# design.net
KiCad netlist of a schematic drawn in Altium Designer
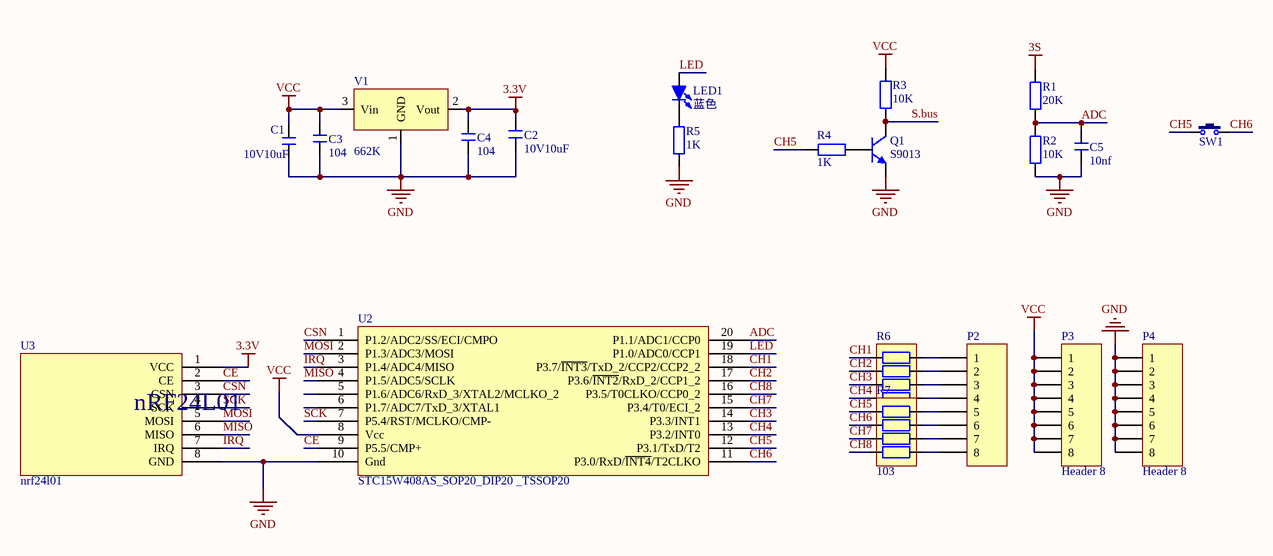
[diagram p0: 原理图.SchDoc]

(export (version "E")
  (design (tool "Eeschema 10.0.6"))
  (components
    (comp (ref "C1")
      (value "10V10uF")
      (footprint "C 0805_L")
      (description "无极性贴片电容")
      (fields (field (name "版权归属") "源创客"))
      (libsource (lib "3.1   - 电阻-电容-电感") (part "C"))
    )
    (comp (ref "C2")
      (value "10V10uF")
      (footprint "C 0805_L")
      (description "无极性贴片电容")
      (fields (field (name "版权归属") "源创客"))
      (libsource (lib "3.1   - 电阻-电容-电感") (part "C"))
    )
    (comp (ref "C3")
      (value "104")
      (footprint "C 0603_L")
      (description "无极性贴片电容")
      (fields (field (name "版权归属") "源创客"))
      (libsource (lib "3.1   - 电阻-电容-电感") (part "C"))
    )
    (comp (ref "C4")
      (value "104")
      (footprint "C 0603_L")
      (description "无极性贴片电容")
      (fields (field (name "版权归属") "源创客"))
      (libsource (lib "3.1   - 电阻-电容-电感") (part "C"))
    )
    (comp (ref "C5")
      (value "10nf")
      (footprint "C 0603_L")
      (description "无极性贴片电容")
      (fields (field (name "版权归属") "源创客"))
      (libsource (lib "3.1   - 电阻-电容-电感") (part "C"))
    )
    (comp (ref "LED1")
      (value "蓝色")
      (footprint "LED 0603B")
      (description "贴片LED")
      (fields (field (name "版权归属") "源创客"))
      (libsource (lib "9.1   - LED") (part "LED-SMD"))
    )
    (comp (ref "P2")
      (value "Header 8")
      (footprint "HDR2.54-LI-8P")
      (description "Header, 8-Pin")
      (fields (field (name "PUBLISHER") "Altium Limited"))
      (libsource (lib "Miscellaneous Connectors") (part "Header 8"))
    )
    (comp (ref "P3")
      (value "Header 8")
      (footprint "HDR2.54-LI-8P")
      (description "Header, 8-Pin")
      (fields (field (name "PUBLISHER") "Altium Limited"))
      (libsource (lib "Miscellaneous Connectors") (part "Header 8"))
    )
    (comp (ref "P4")
      (value "Header 8")
      (footprint "HDR2.54-LI-8P")
      (description "Header, 8-Pin")
      (fields (field (name "PUBLISHER") "Altium Limited"))
      (libsource (lib "Miscellaneous Connectors") (part "Header 8"))
    )
    (comp (ref "Q1")
      (value "S9013")
      (footprint "SOT23-3N")
      (description "低频放大-NPN型")
      (fields (field (name "版权归属") "源创客"))
      (libsource (lib "6.2   - 三极管") (part "9013-SMD"))
    )
    (comp (ref "R1")
      (value "20K")
      (footprint "R 0603_L")
      (description "贴片电阻")
      (fields (field (name "版权归属") "源创客"))
      (libsource (lib "3.1   - 电阻-电容-电感") (part "R"))
    )
    (comp (ref "R2")
      (value "10K")
      (footprint "R 0603_L")
      (description "贴片电阻")
      (fields (field (name "版权归属") "源创客"))
      (libsource (lib "3.1   - 电阻-电容-电感") (part "R"))
    )
    (comp (ref "R3")
      (value "10K")
      (footprint "R 0603_L")
      (description "贴片电阻")
      (fields (field (name "版权归属") "源创客"))
      (libsource (lib "3.1   - 电阻-电容-电感") (part "R"))
    )
    (comp (ref "R4")
      (value "1K")
      (footprint "R 0603_L")
      (description "贴片电阻")
      (fields (field (name "版权归属") "源创客"))
      (libsource (lib "3.1   - 电阻-电容-电感") (part "R"))
    )
    (comp (ref "R5")
      (value "1K")
      (footprint "R 0603_L")
      (description "贴片电阻")
      (fields (field (name "版权归属") "源创客"))
      (libsource (lib "3.1   - 电阻-电容-电感") (part "R"))
    )
    (comp (ref "R6")
      (value "103")
      (footprint "RCA-8P4R-0603")
      (description "贴片网络排阻")
      (fields (field (name "版权归属") "源创客"))
      (libsource (lib "3.1   - 电阻-电容-电感") (part "R-8P4R"))
    )
    (comp (ref "R7")
      (value "103")
      (footprint "RCA-8P4R-0603")
      (description "贴片网络排阻")
      (fields (field (name "版权归属") "源创客"))
      (libsource (lib "3.1   - 电阻-电容-电感") (part "R-8P4R"))
    )
    (comp (ref "SW1")
      (value "3x6x5")
      (footprint "SW_1")
      (description "3x6轻触开关")
      (fields (field (name "版权归属") "源创客"))
      (libsource (lib "5.1   - 按键-开关") (part "TSW 3x6"))
    )
    (comp (ref "U2")
      (value "STC15W408AS_SOP20_DIP20 _TSSOP20")
      (footprint "TSSOP20_N")
      (libsource (lib "stcmcu_altium_lib") (part "STC15W401AS_SOP20_DIP20 _TSSOP20"))
    )
    (comp (ref "U3")
      (value "nrf24l01")
      (footprint "NRF24L01_4to1")
      (libsource (lib "原理图库文件") (part "nrf24l01"))
    )
    (comp (ref "V1") (value "662K") (footprint "SOT23-3L") (libsource (lib "MySchLib") (part "662K")))
  )
  (nets
    (net (code "1") (name "/ADC") (class "Default")
      (node (ref "C5") (pin "1") (pinfunction "1_1") (pintype "passive"))
      (node (ref "R1") (pin "2") (pinfunction "2_2") (pintype "passive"))
      (node (ref "R2") (pin "2") (pinfunction "2_2") (pintype "passive"))
      (node (ref "U2") (pin "20") (pinfunction "P1.1/ADC1/CCP0_20") (pintype "passive"))
    )
    (net (code "2") (name "/CE") (class "Default")
      (node (ref "U2") (pin "9") (pinfunction "P5.5/CMP+_9") (pintype "passive"))
      (node (ref "U3") (pin "2") (pinfunction "CE_2") (pintype "passive"))
    )
    (net (code "3") (name "/CH1") (class "Default")
      (node (ref "R6") (pin "1") (pinfunction "1_1") (pintype "passive"))
      (node (ref "U2") (pin "18") (pinfunction "P3.7/~{INT3}/TxD_2/CCP2/CCP2_2_18") (pintype "passive"))
    )
    (net (code "4") (name "/CH2") (class "Default")
      (node (ref "R6") (pin "2") (pinfunction "2_2") (pintype "passive"))
      (node (ref "U2") (pin "17") (pinfunction "P3.6/~{INT2}/RxD_2/CCP1_2_17") (pintype "passive"))
    )
    (net (code "5") (name "/CH3") (class "Default")
      (node (ref "R6") (pin "3") (pinfunction "3_3") (pintype "passive"))
      (node (ref "U2") (pin "14") (pinfunction "P3.3/INT1_14") (pintype "passive"))
    )
    (net (code "6") (name "/CH4") (class "Default")
      (node (ref "R6") (pin "4") (pinfunction "4_4") (pintype "passive"))
      (node (ref "U2") (pin "13") (pinfunction "P3.2/INT0_13") (pintype "passive"))
    )
    (net (code "7") (name "/CH5") (class "Default")
      (node (ref "R4") (pin "1") (pinfunction "1_1") (pintype "passive"))
      (node (ref "R7") (pin "1") (pinfunction "1_1") (pintype "passive"))
      (node (ref "SW1") (pin "1") (pinfunction "1_1") (pintype "passive"))
      (node (ref "U2") (pin "12") (pinfunction "P3.1/TxD/T2_12") (pintype "passive"))
    )
    (net (code "8") (name "/CH6") (class "Default")
      (node (ref "R7") (pin "2") (pinfunction "2_2") (pintype "passive"))
      (node (ref "SW1") (pin "2") (pinfunction "2_2") (pintype "passive"))
      (node (ref "U2") (pin "11") (pinfunction "P3.0/RxD/~{INT4}/T2CLKO_11") (pintype "passive"))
    )
    (net (code "9") (name "/CH7") (class "Default")
      (node (ref "R7") (pin "3") (pinfunction "3_3") (pintype "passive"))
      (node (ref "U2") (pin "15") (pinfunction "P3.4/T0/ECI_2_15") (pintype "passive"))
    )
    (net (code "10") (name "/CH8") (class "Default")
      (node (ref "R7") (pin "4") (pinfunction "4_4") (pintype "passive"))
      (node (ref "U2") (pin "16") (pinfunction "P3.5/T0CLKO/CCP0_2_16") (pintype "passive"))
    )
    (net (code "11") (name "/CSN") (class "Default")
      (node (ref "U2") (pin "1") (pinfunction "P1.2/ADC2/SS/ECI/CMPO_1") (pintype "passive"))
      (node (ref "U3") (pin "3") (pinfunction "CSN_3") (pintype "passive"))
    )
    (net (code "12") (name "/IRQ") (class "Default")
      (node (ref "U2") (pin "3") (pinfunction "P1.4/ADC4/MISO_3") (pintype "passive"))
      (node (ref "U3") (pin "7") (pinfunction "IRQ_7") (pintype "power_in"))
    )
    (net (code "13") (name "/LED") (class "Default")
      (node (ref "LED1") (pin "1") (pinfunction "A_1") (pintype "passive"))
      (node (ref "U2") (pin "19") (pinfunction "P1.0/ADC0/CCP1_19") (pintype "passive"))
    )
    (net (code "14") (name "/MISO") (class "Default")
      (node (ref "U2") (pin "4") (pinfunction "P1.5/ADC5/SCLK_4") (pintype "passive"))
      (node (ref "U3") (pin "6") (pinfunction "MISO_6") (pintype "passive"))
    )
    (net (code "15") (name "/MOSI") (class "Default")
      (node (ref "U2") (pin "2") (pinfunction "P1.3/ADC3/MOSI_2") (pintype "passive"))
      (node (ref "U3") (pin "5") (pinfunction "MOSI_5") (pintype "passive"))
    )
    (net (code "16") (name "/S.bus") (class "Default")
      (node (ref "Q1") (pin "3") (pinfunction "C_3") (pintype "passive"))
      (node (ref "R3") (pin "1") (pinfunction "1_1") (pintype "passive"))
    )
    (net (code "17") (name "/SCK") (class "Default")
      (node (ref "U2") (pin "7") (pinfunction "P5.4/RST/MCLKO/CMP-_7") (pintype "passive"))
      (node (ref "U3") (pin "4") (pinfunction "SCK_4") (pintype "passive"))
    )
    (net (code "18") (name "3.3V") (class "Default")
      (node (ref "C2") (pin "2") (pinfunction "2_2") (pintype "passive"))
      (node (ref "C4") (pin "2") (pinfunction "2_2") (pintype "passive"))
      (node (ref "U3") (pin "1") (pinfunction "VCC_1") (pintype "passive"))
      (node (ref "V1") (pin "2") (pinfunction "Vout_2") (pintype "passive"))
    )
    (net (code "19") (name "3S") (class "Default")
      (node (ref "R1") (pin "1") (pinfunction "1_1") (pintype "passive"))
    )
    (net (code "20") (name "GND") (class "Default")
      (node (ref "C1") (pin "1") (pinfunction "1_1") (pintype "passive"))
      (node (ref "C2") (pin "1") (pinfunction "1_1") (pintype "passive"))
      (node (ref "C3") (pin "1") (pinfunction "1_1") (pintype "passive"))
      (node (ref "C4") (pin "1") (pinfunction "1_1") (pintype "passive"))
      (node (ref "C5") (pin "2") (pinfunction "2_2") (pintype "passive"))
      (node (ref "P4") (pin "1") (pinfunction "1_1") (pintype "passive"))
      (node (ref "P4") (pin "2") (pinfunction "2_2") (pintype "passive"))
      (node (ref "P4") (pin "3") (pinfunction "3_3") (pintype "passive"))
      (node (ref "P4") (pin "4") (pinfunction "4_4") (pintype "passive"))
      (node (ref "P4") (pin "5") (pinfunction "5_5") (pintype "passive"))
      (node (ref "P4") (pin "6") (pinfunction "6_6") (pintype "passive"))
      (node (ref "P4") (pin "7") (pinfunction "7_7") (pintype "passive"))
      (node (ref "P4") (pin "8") (pinfunction "8_8") (pintype "passive"))
      (node (ref "Q1") (pin "2") (pinfunction "E_2") (pintype "passive"))
      (node (ref "R2") (pin "1") (pinfunction "1_1") (pintype "passive"))
      (node (ref "R5") (pin "1") (pinfunction "1_1") (pintype "passive"))
      (node (ref "U2") (pin "10") (pinfunction "Gnd_10") (pintype "passive"))
      (node (ref "U3") (pin "8") (pinfunction "GND_8") (pintype "passive"))
      (node (ref "V1") (pin "1") (pinfunction "GND_1") (pintype "passive"))
    )
    (net (code "21") (name "Net-(LED1-K)") (class "Default")
      (node (ref "LED1") (pin "2") (pinfunction "K_2") (pintype "passive"))
      (node (ref "R5") (pin "2") (pinfunction "2_2") (pintype "passive"))
    )
    (net (code "22") (name "Net-(P2-Pad1)") (class "Default")
      (node (ref "P2") (pin "1") (pinfunction "1_1") (pintype "passive"))
      (node (ref "R6") (pin "8") (pinfunction "8_8") (pintype "passive"))
    )
    (net (code "23") (name "Net-(P2-Pad2)") (class "Default")
      (node (ref "P2") (pin "2") (pinfunction "2_2") (pintype "passive"))
      (node (ref "R6") (pin "7") (pinfunction "7_7") (pintype "passive"))
    )
    (net (code "24") (name "Net-(P2-Pad3)") (class "Default")
      (node (ref "P2") (pin "3") (pinfunction "3_3") (pintype "passive"))
      (node (ref "R6") (pin "6") (pinfunction "6_6") (pintype "passive"))
    )
    (net (code "25") (name "Net-(P2-Pad4)") (class "Default")
      (node (ref "P2") (pin "4") (pinfunction "4_4") (pintype "passive"))
      (node (ref "R6") (pin "5") (pinfunction "5_5") (pintype "passive"))
    )
    (net (code "26") (name "Net-(P2-Pad5)") (class "Default")
      (node (ref "P2") (pin "5") (pinfunction "5_5") (pintype "passive"))
      (node (ref "R7") (pin "8") (pinfunction "8_8") (pintype "passive"))
    )
    (net (code "27") (name "Net-(P2-Pad6)") (class "Default")
      (node (ref "P2") (pin "6") (pinfunction "6_6") (pintype "passive"))
      (node (ref "R7") (pin "7") (pinfunction "7_7") (pintype "passive"))
    )
    (net (code "28") (name "Net-(P2-Pad7)") (class "Default")
      (node (ref "P2") (pin "7") (pinfunction "7_7") (pintype "passive"))
      (node (ref "R7") (pin "6") (pinfunction "6_6") (pintype "passive"))
    )
    (net (code "29") (name "Net-(P2-Pad8)") (class "Default")
      (node (ref "P2") (pin "8") (pinfunction "8_8") (pintype "passive"))
      (node (ref "R7") (pin "5") (pinfunction "5_5") (pintype "passive"))
    )
    (net (code "30") (name "Net-(Q1-B)") (class "Default")
      (node (ref "Q1") (pin "1") (pinfunction "B_1") (pintype "passive"))
      (node (ref "R4") (pin "2") (pinfunction "2_2") (pintype "passive"))
    )
    (net (code "31") (name "VCC") (class "Default")
      (node (ref "C1") (pin "2") (pinfunction "2_2") (pintype "passive"))
      (node (ref "C3") (pin "2") (pinfunction "2_2") (pintype "passive"))
      (node (ref "P3") (pin "1") (pinfunction "1_1") (pintype "passive"))
      (node (ref "P3") (pin "2") (pinfunction "2_2") (pintype "passive"))
      (node (ref "P3") (pin "3") (pinfunction "3_3") (pintype "passive"))
      (node (ref "P3") (pin "4") (pinfunction "4_4") (pintype "passive"))
      (node (ref "P3") (pin "5") (pinfunction "5_5") (pintype "passive"))
      (node (ref "P3") (pin "6") (pinfunction "6_6") (pintype "passive"))
      (node (ref "P3") (pin "7") (pinfunction "7_7") (pintype "passive"))
      (node (ref "P3") (pin "8") (pinfunction "8_8") (pintype "passive"))
      (node (ref "R3") (pin "2") (pinfunction "2_2") (pintype "passive"))
      (node (ref "U2") (pin "8") (pinfunction "Vcc_8") (pintype "passive"))
      (node (ref "V1") (pin "3") (pinfunction "Vin_3") (pintype "passive"))
    )
    (net (code "32") (name "unconnected-(U2-P1.6{slash}ADC6{slash}RxD_3{slash}XTAL2{slash}MCLKO_2-Pad5)") (class "Default")
      (node (ref "U2") (pin "5") (pinfunction "P1.6/ADC6/RxD_3/XTAL2/MCLKO_2_5") (pintype "passive"))
    )
    (net (code "33") (name "unconnected-(U2-P1.7{slash}ADC7{slash}TxD_3{slash}XTAL1-Pad6)") (class "Default")
      (node (ref "U2") (pin "6") (pinfunction "P1.7/ADC7/TxD_3/XTAL1_6") (pintype "passive"))
    )
  )
)
